# 6P_JST-PH_EXT.net
KiCad netlist of a schematic drawn in Altium Designer
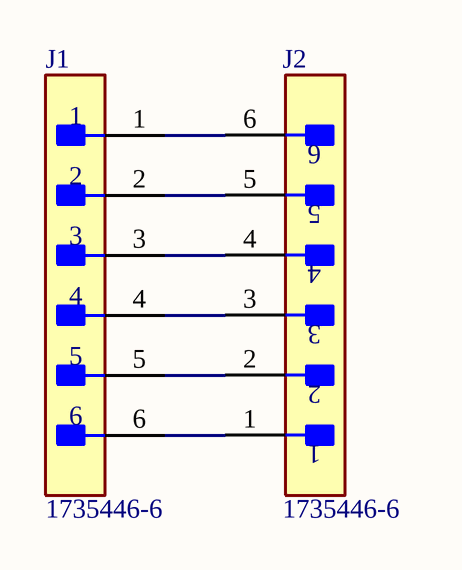
[diagram p0: 6P_JST-PH_EXT.SchDoc]

(export (version "E")
  (design (tool "Eeschema 10.0.6"))
  (components
    (comp (ref "J1")
      (value "1735446-6")
      (footprint "FP-1735446-6-MFG")
      (description "CONN HEADER VERT 6POS 2MM")
      (fields
        (field (name "MANUFACTURER") "TE")
        (field (name "OCTOPART") "https://octopart.com/1735446-6-te+connectivity-42205942")
      )
      (libsource (lib "") (part "f2cb566baf1c37ab5a3b8e90bbeafd6_1"))
    )
    (comp (ref "J2")
      (value "1735446-6")
      (footprint "FP-1735446-6-MFG")
      (description "CONN HEADER VERT 6POS 2MM")
      (fields
        (field (name "MANUFACTURER") "TE")
        (field (name "OCTOPART") "https://octopart.com/1735446-6-te+connectivity-42205942")
      )
      (libsource (lib "Altium Content Vault") (part "f2cb566baf1c37ab5a3b8e90bbeafd6"))
    )
  )
  (nets
    (net (code "1") (name "Net-(J1-Pad1)") (class "Default")
      (node (ref "J1") (pin "1") (pinfunction "1_1") (pintype "passive"))
      (node (ref "J2") (pin "6") (pinfunction "6_6") (pintype "passive"))
    )
    (net (code "2") (name "Net-(J1-Pad2)") (class "Default")
      (node (ref "J1") (pin "2") (pinfunction "2_2") (pintype "passive"))
      (node (ref "J2") (pin "5") (pinfunction "5_5") (pintype "passive"))
    )
    (net (code "3") (name "Net-(J1-Pad3)") (class "Default")
      (node (ref "J1") (pin "3") (pinfunction "3_3") (pintype "passive"))
      (node (ref "J2") (pin "4") (pinfunction "4_4") (pintype "passive"))
    )
    (net (code "4") (name "Net-(J1-Pad4)") (class "Default")
      (node (ref "J1") (pin "4") (pinfunction "4_4") (pintype "passive"))
      (node (ref "J2") (pin "3") (pinfunction "3_3") (pintype "passive"))
    )
    (net (code "5") (name "Net-(J1-Pad5)") (class "Default")
      (node (ref "J1") (pin "5") (pinfunction "5_5") (pintype "passive"))
      (node (ref "J2") (pin "2") (pinfunction "2_2") (pintype "passive"))
    )
    (net (code "6") (name "Net-(J1-Pad6)") (class "Default")
      (node (ref "J1") (pin "6") (pinfunction "6_6") (pintype "passive"))
      (node (ref "J2") (pin "1") (pinfunction "1_1") (pintype "passive"))
    )
  )
)
